# power.net
KiCad netlist of a schematic drawn in Altium Designer
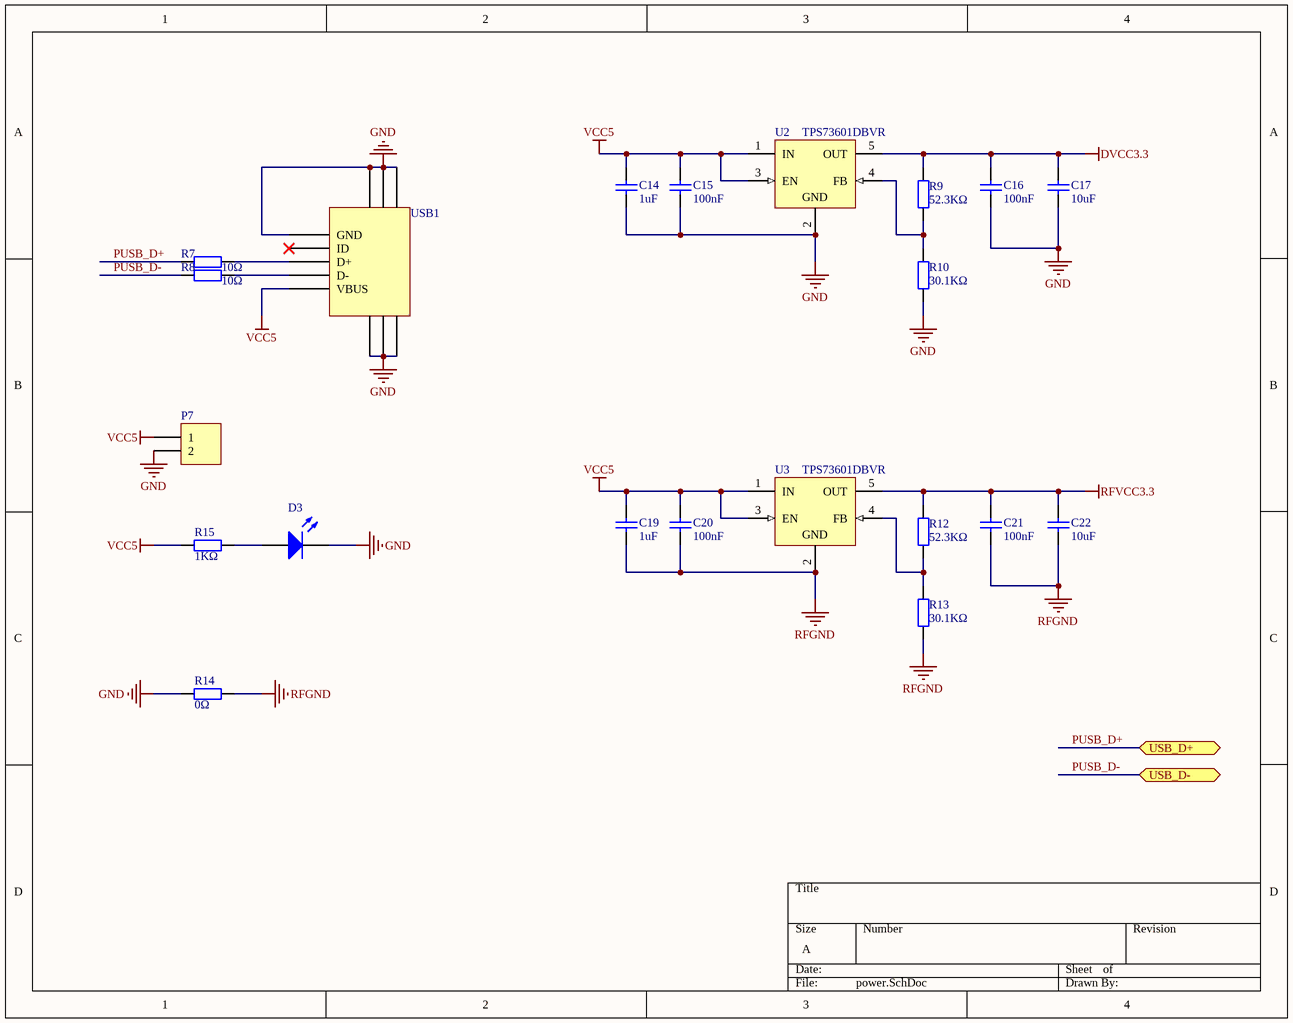
[diagram p0: power.SchDoc]

(export (version "E")
  (design (tool "Eeschema 10.0.6"))
  (components
    (comp (ref "C14")
      (value "1uF")
      (footprint "0603_C")
      (description "贴片电容")
      (libsource (lib "Miscellaneous Devices LC") (part "0603 1uF (105) 10% 50V"))
    )
    (comp (ref "C15")
      (value "100nF")
      (footprint "0603_C")
      (description "贴片电容")
      (libsource (lib "Miscellaneous Devices LC") (part "0603 100nF (104) 10% 50V"))
    )
    (comp (ref "C16")
      (value "100nF")
      (footprint "0603_C")
      (description "贴片电容")
      (libsource (lib "Miscellaneous Devices LC") (part "0603 100nF (104) 10% 50V"))
    )
    (comp (ref "C17")
      (value "10uF")
      (footprint "0603_C")
      (description "贴片电容")
      (libsource (lib "Miscellaneous Devices LC") (part "0603 10uF (106) 10% 10V"))
    )
    (comp (ref "C19")
      (value "1uF")
      (footprint "0603_C")
      (description "贴片电容")
      (libsource (lib "Miscellaneous Devices LC") (part "0603 1uF (105) 10% 50V"))
    )
    (comp (ref "C20")
      (value "100nF")
      (footprint "0603_C")
      (description "贴片电容")
      (libsource (lib "Miscellaneous Devices LC") (part "0603 100nF (104) 10% 50V"))
    )
    (comp (ref "C21")
      (value "100nF")
      (footprint "0603_C")
      (description "贴片电容")
      (libsource (lib "Miscellaneous Devices LC") (part "0603 100nF (104) 10% 50V"))
    )
    (comp (ref "C22")
      (value "10uF")
      (footprint "0603_C")
      (description "贴片电容")
      (libsource (lib "Miscellaneous Devices LC") (part "0603 10uF (106) 10% 10V"))
    )
    (comp (ref "D3")
      (value "蓝灯 0805")
      (footprint "0805_LED_S1")
      (description "发光二极管")
      (libsource (lib "Miscellaneous Devices LC") (part "0805 蓝灯"))
    )
    (comp (ref "P7")
      (value "Header 2")
      (footprint "HDR1X2")
      (description "Header, 2-Pin")
      (fields (field (name "PUBLISHER") "Altium Limited"))
      (libsource (lib "Miscellaneous Connectors") (part "Header 2"))
    )
    (comp (ref "R7")
      (value "10Ω")
      (footprint "0603_R")
      (description "贴片电阻")
      (libsource (lib "Miscellaneous Devices LC") (part "0603 10Ω (10R0) 1%"))
    )
    (comp (ref "R8")
      (value "10Ω")
      (footprint "0603_R")
      (description "贴片电阻")
      (libsource (lib "Miscellaneous Devices LC") (part "0603 10Ω (10R0) 1%"))
    )
    (comp (ref "R9")
      (value "52.3KΩ")
      (footprint "0603_R")
      (description "贴片电阻")
      (libsource (lib "Miscellaneous Devices LC") (part "0603 51KΩ (5102) 1%"))
    )
    (comp (ref "R10")
      (value "30.1KΩ")
      (footprint "0603_R")
      (description "贴片电阻")
      (libsource (lib "Miscellaneous Devices LC") (part "0603 30KΩ (3002) 1%"))
    )
    (comp (ref "R12")
      (value "52.3KΩ")
      (footprint "0603_R")
      (description "贴片电阻")
      (libsource (lib "Miscellaneous Devices LC") (part "0603 51KΩ (5102) 1%"))
    )
    (comp (ref "R13")
      (value "30.1KΩ")
      (footprint "0603_R")
      (description "贴片电阻")
      (libsource (lib "Miscellaneous Devices LC") (part "0603 30KΩ (3002) 1%"))
    )
    (comp (ref "R14")
      (value "0Ω")
      (footprint "0603_R")
      (description "贴片电阻")
      (libsource (lib "Miscellaneous Devices LC") (part "0603 0Ω (0R0) 1%"))
    )
    (comp (ref "R15")
      (value "1KΩ")
      (footprint "0603_R")
      (description "贴片电阻")
      (libsource (lib "Miscellaneous Devices LC") (part "0603 1KΩ (1001) 1%"))
    )
    (comp (ref "U2")
      (value "TPS73601DBVR")
      (footprint "TI-DBV5_L")
      (fields (field (name "MANUFACTURER") "Texas Instruments"))
      (libsource (lib "TI Power Management Linear Regulator Single Channel LDO (400-7500mA)") (part "TPS73601DBVR"))
    )
    (comp (ref "U3")
      (value "TPS73601DBVR")
      (footprint "TI-DBV5_L")
      (fields (field (name "MANUFACTURER") "Texas Instruments"))
      (libsource (lib "TI Power Management Linear Regulator Single Channel LDO (400-7500mA)") (part "TPS73601DBVR"))
    )
    (comp (ref "USB1")
      (value "USB Micro B 1A")
      (footprint "MICRO-USB-1")
      (libsource (lib "Miscellaneous Connectors") (part "MICRO 5PFemaleBtype"))
    )
  )
  (nets
    (net (code "1") (name "/PUSB_D+") (class "Default")
      (node (ref "R7") (pin "1") (pinfunction "1_1") (pintype "passive"))
    )
    (net (code "2") (name "/PUSB_D-") (class "Default")
      (node (ref "R8") (pin "1") (pinfunction "1_1") (pintype "passive"))
    )
    (net (code "3") (name "DVCC3.3") (class "Default")
      (node (ref "C16") (pin "2") (pinfunction "2_2") (pintype "passive"))
      (node (ref "C17") (pin "2") (pinfunction "2_2") (pintype "passive"))
      (node (ref "R9") (pin "2") (pinfunction "2_2") (pintype "passive"))
      (node (ref "U2") (pin "5") (pinfunction "OUT_5") (pintype "power_in"))
    )
    (net (code "4") (name "GND") (class "Default")
      (node (ref "C14") (pin "1") (pinfunction "1_1") (pintype "passive"))
      (node (ref "C15") (pin "1") (pinfunction "1_1") (pintype "passive"))
      (node (ref "C16") (pin "1") (pinfunction "1_1") (pintype "passive"))
      (node (ref "C17") (pin "1") (pinfunction "1_1") (pintype "passive"))
      (node (ref "D3") (pin "K") (pinfunction "K_K") (pintype "passive"))
      (node (ref "P7") (pin "2") (pinfunction "2_2") (pintype "passive"))
      (node (ref "R10") (pin "1") (pinfunction "1_1") (pintype "passive"))
      (node (ref "R14") (pin "1") (pinfunction "1_1") (pintype "passive"))
      (node (ref "U2") (pin "2") (pinfunction "GND_2") (pintype "power_in"))
      (node (ref "USB1") (pin "0") (pinfunction "0_0") (pintype "passive"))
      (node (ref "USB1") (pin "5") (pinfunction "GND_5") (pintype "passive"))
    )
    (net (code "5") (name "Net-(D3-PadA)") (class "Default")
      (node (ref "D3") (pin "A") (pinfunction "A_A") (pintype "passive"))
      (node (ref "R15") (pin "2") (pinfunction "2_2") (pintype "passive"))
    )
    (net (code "6") (name "Net-(U2-FB)") (class "Default")
      (node (ref "R10") (pin "2") (pinfunction "2_2") (pintype "passive"))
      (node (ref "R9") (pin "1") (pinfunction "1_1") (pintype "passive"))
      (node (ref "U2") (pin "4") (pinfunction "FB_4") (pintype "input"))
    )
    (net (code "7") (name "Net-(U3-FB)") (class "Default")
      (node (ref "R12") (pin "1") (pinfunction "1_1") (pintype "passive"))
      (node (ref "R13") (pin "2") (pinfunction "2_2") (pintype "passive"))
      (node (ref "U3") (pin "4") (pinfunction "FB_4") (pintype "input"))
    )
    (net (code "8") (name "Net-(USB1-D+)") (class "Default")
      (node (ref "R7") (pin "2") (pinfunction "2_2") (pintype "passive"))
      (node (ref "USB1") (pin "3") (pinfunction "D+_3") (pintype "passive"))
    )
    (net (code "9") (name "Net-(USB1-D-)") (class "Default")
      (node (ref "R8") (pin "2") (pinfunction "2_2") (pintype "passive"))
      (node (ref "USB1") (pin "2") (pinfunction "D-_2") (pintype "passive"))
    )
    (net (code "10") (name "RFGND") (class "Default")
      (node (ref "C19") (pin "1") (pinfunction "1_1") (pintype "passive"))
      (node (ref "C20") (pin "1") (pinfunction "1_1") (pintype "passive"))
      (node (ref "C21") (pin "1") (pinfunction "1_1") (pintype "passive"))
      (node (ref "C22") (pin "1") (pinfunction "1_1") (pintype "passive"))
      (node (ref "R13") (pin "1") (pinfunction "1_1") (pintype "passive"))
      (node (ref "R14") (pin "2") (pinfunction "2_2") (pintype "passive"))
      (node (ref "U3") (pin "2") (pinfunction "GND_2") (pintype "power_in"))
    )
    (net (code "11") (name "RFVCC3.3") (class "Default")
      (node (ref "C21") (pin "2") (pinfunction "2_2") (pintype "passive"))
      (node (ref "C22") (pin "2") (pinfunction "2_2") (pintype "passive"))
      (node (ref "R12") (pin "2") (pinfunction "2_2") (pintype "passive"))
      (node (ref "U3") (pin "5") (pinfunction "OUT_5") (pintype "power_in"))
    )
    (net (code "12") (name "VCC5") (class "Default")
      (node (ref "C14") (pin "2") (pinfunction "2_2") (pintype "passive"))
      (node (ref "C15") (pin "2") (pinfunction "2_2") (pintype "passive"))
      (node (ref "C19") (pin "2") (pinfunction "2_2") (pintype "passive"))
      (node (ref "C20") (pin "2") (pinfunction "2_2") (pintype "passive"))
      (node (ref "P7") (pin "1") (pinfunction "1_1") (pintype "passive"))
      (node (ref "R15") (pin "1") (pinfunction "1_1") (pintype "passive"))
      (node (ref "U2") (pin "1") (pinfunction "IN_1") (pintype "power_in"))
      (node (ref "U2") (pin "3") (pinfunction "EN_3") (pintype "input"))
      (node (ref "U3") (pin "1") (pinfunction "IN_1") (pintype "power_in"))
      (node (ref "U3") (pin "3") (pinfunction "EN_3") (pintype "input"))
      (node (ref "USB1") (pin "1") (pinfunction "VBUS_1") (pintype "passive"))
    )
    (net (code "13") (name "unconnected-(USB1-ID-Pad4)") (class "Default")
      (node (ref "USB1") (pin "4") (pinfunction "ID_4") (pintype "passive+no_connect"))
    )
  )
)
